# LineMixer_v1_0.net
KiCad netlist of a schematic drawn in EAGLE
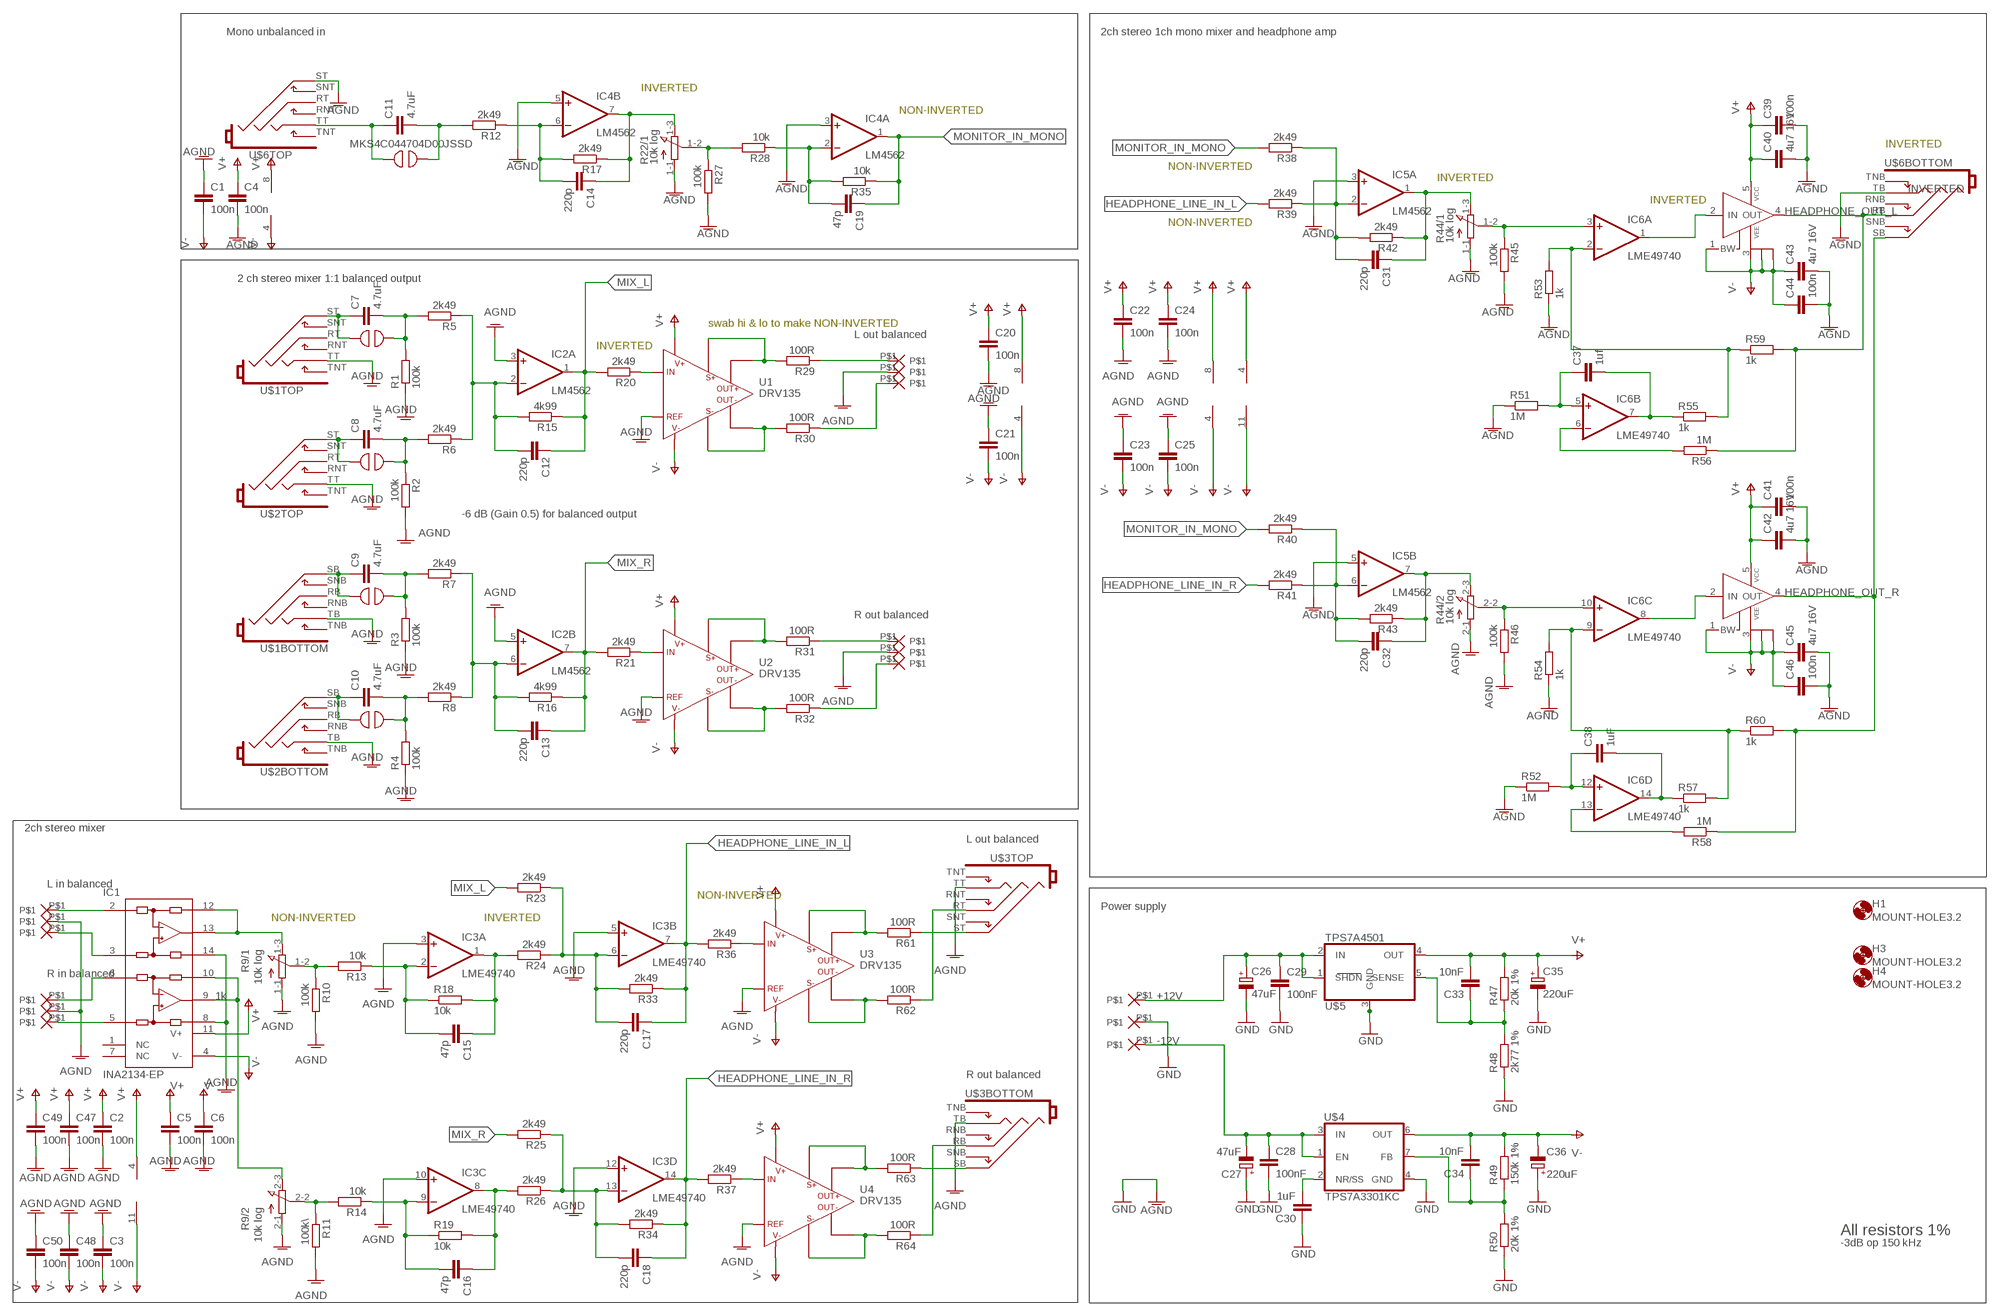
[diagram p0: schematic, sheet 1]

(export (version "E")
  (design (tool "Eeschema 10.0.6"))
  (components
    (comp (ref "C1")
      (value "100n")
      (footprint "eagle-import:C0603")
      (libsource (lib "eagle-import") (part "C-EUC0603"))
    )
    (comp (ref "C2")
      (value "100n")
      (footprint "eagle-import:C0603")
      (libsource (lib "eagle-import") (part "C-EUC0603"))
    )
    (comp (ref "C3")
      (value "100n")
      (footprint "eagle-import:C0603")
      (libsource (lib "eagle-import") (part "C-EUC0603"))
    )
    (comp (ref "C4")
      (value "100n")
      (footprint "eagle-import:C0603")
      (libsource (lib "eagle-import") (part "C-EUC0603"))
    )
    (comp (ref "C5")
      (value "100n")
      (footprint "eagle-import:C0603")
      (libsource (lib "eagle-import") (part "C-EUC0603"))
    )
    (comp (ref "C6")
      (value "100n")
      (footprint "eagle-import:C0603")
      (libsource (lib "eagle-import") (part "C-EUC0603"))
    )
    (comp (ref "C7")
      (value "4.7uF")
      (footprint "eagle-import:C15B7")
      (libsource (lib "eagle-import") (part "C15/7"))
    )
    (comp (ref "C8")
      (value "4.7uF")
      (footprint "eagle-import:C15B7")
      (libsource (lib "eagle-import") (part "C15/7"))
    )
    (comp (ref "C9")
      (value "4.7uF")
      (footprint "eagle-import:C15B7")
      (libsource (lib "eagle-import") (part "C15/7"))
    )
    (comp (ref "C10")
      (value "4.7uF")
      (footprint "eagle-import:C15B7")
      (libsource (lib "eagle-import") (part "C15/7"))
    )
    (comp (ref "C11")
      (value "4.7uF")
      (footprint "eagle-import:C15B7")
      (libsource (lib "eagle-import") (part "C15/7"))
    )
    (comp (ref "C12")
      (value "220p")
      (footprint "eagle-import:C0603K")
      (libsource (lib "eagle-import") (part "C-EUC0603K"))
    )
    (comp (ref "C13")
      (value "220p")
      (footprint "eagle-import:C0603K")
      (libsource (lib "eagle-import") (part "C-EUC0603K"))
    )
    (comp (ref "C14")
      (value "220p")
      (footprint "eagle-import:C0603K")
      (libsource (lib "eagle-import") (part "C-EUC0603K"))
    )
    (comp (ref "C15")
      (value "47p")
      (footprint "eagle-import:C0603K")
      (libsource (lib "eagle-import") (part "C-EUC0603K"))
    )
    (comp (ref "C16")
      (value "47p")
      (footprint "eagle-import:C0603K")
      (libsource (lib "eagle-import") (part "C-EUC0603K"))
    )
    (comp (ref "C17")
      (value "220p")
      (footprint "eagle-import:C0603K")
      (libsource (lib "eagle-import") (part "C-EUC0603K"))
    )
    (comp (ref "C18")
      (value "220p")
      (footprint "eagle-import:C0603K")
      (libsource (lib "eagle-import") (part "C-EUC0603K"))
    )
    (comp (ref "C19")
      (value "47p")
      (footprint "eagle-import:C0603K")
      (libsource (lib "eagle-import") (part "C-EUC0603K"))
    )
    (comp (ref "C20")
      (value "100n")
      (footprint "eagle-import:C0603")
      (libsource (lib "eagle-import") (part "C-EUC0603"))
    )
    (comp (ref "C21")
      (value "100n")
      (footprint "eagle-import:C0603")
      (libsource (lib "eagle-import") (part "C-EUC0603"))
    )
    (comp (ref "C22")
      (value "100n")
      (footprint "eagle-import:C0603")
      (libsource (lib "eagle-import") (part "C-EUC0603"))
    )
    (comp (ref "C23")
      (value "100n")
      (footprint "eagle-import:C0603")
      (libsource (lib "eagle-import") (part "C-EUC0603"))
    )
    (comp (ref "C24")
      (value "100n")
      (footprint "eagle-import:C0603")
      (libsource (lib "eagle-import") (part "C-EUC0603"))
    )
    (comp (ref "C25")
      (value "100n")
      (footprint "eagle-import:C0603")
      (libsource (lib "eagle-import") (part "C-EUC0603"))
    )
    (comp (ref "C26")
      (value "47uF")
      (footprint "eagle-import:D_7343-31R")
      (libsource (lib "eagle-import") (part "CPOL-EUD/7343-31R"))
    )
    (comp (ref "C27")
      (value "47uF")
      (footprint "eagle-import:D_7343-31R")
      (libsource (lib "eagle-import") (part "CPOL-EUD/7343-31R"))
    )
    (comp (ref "C28")
      (value "100nF")
      (footprint "eagle-import:C0603")
      (libsource (lib "eagle-import") (part "C-EUC0603"))
    )
    (comp (ref "C29")
      (value "100nF")
      (footprint "eagle-import:C0603")
      (libsource (lib "eagle-import") (part "C-EUC0603"))
    )
    (comp (ref "C30")
      (value "1uF")
      (footprint "eagle-import:C0603")
      (libsource (lib "eagle-import") (part "C-EUC0603"))
    )
    (comp (ref "C31")
      (value "220p")
      (footprint "eagle-import:C0603K")
      (libsource (lib "eagle-import") (part "C-EUC0603K"))
    )
    (comp (ref "C32")
      (value "220p")
      (footprint "eagle-import:C0603K")
      (libsource (lib "eagle-import") (part "C-EUC0603K"))
    )
    (comp (ref "C33")
      (value "10nF")
      (footprint "eagle-import:C0603")
      (libsource (lib "eagle-import") (part "C-EUC0603"))
    )
    (comp (ref "C34")
      (value "10nF")
      (footprint "eagle-import:C0603")
      (libsource (lib "eagle-import") (part "C-EUC0603"))
    )
    (comp (ref "C35")
      (value "220uF")
      (footprint "eagle-import:D_7343-31R")
      (libsource (lib "eagle-import") (part "CPOL-EUD/7343-31R"))
    )
    (comp (ref "C36")
      (value "220uF")
      (footprint "eagle-import:D_7343-31R")
      (libsource (lib "eagle-import") (part "CPOL-EUD/7343-31R"))
    )
    (comp (ref "C37")
      (value "1uf")
      (footprint "eagle-import:C0603")
      (libsource (lib "eagle-import") (part "C-EUC0603"))
    )
    (comp (ref "C38")
      (value "1uF")
      (footprint "eagle-import:C0603")
      (libsource (lib "eagle-import") (part "C-EUC0603"))
    )
    (comp (ref "C39")
      (value "100n")
      (footprint "eagle-import:C0603")
      (libsource (lib "eagle-import") (part "C-EUC0603"))
    )
    (comp (ref "C40")
      (value "4u7 16V")
      (footprint "eagle-import:C1206")
      (libsource (lib "eagle-import") (part "C-EUC1206"))
    )
    (comp (ref "C41")
      (value "100n")
      (footprint "eagle-import:C0603")
      (libsource (lib "eagle-import") (part "C-EUC0603"))
    )
    (comp (ref "C42")
      (value "4u7 16V")
      (footprint "eagle-import:C1206")
      (libsource (lib "eagle-import") (part "C-EUC1206"))
    )
    (comp (ref "C43")
      (value "4u7 16V")
      (footprint "eagle-import:C1206")
      (libsource (lib "eagle-import") (part "C-EUC1206"))
    )
    (comp (ref "C44")
      (value "100n")
      (footprint "eagle-import:C0603")
      (libsource (lib "eagle-import") (part "C-EUC0603"))
    )
    (comp (ref "C45")
      (value "4u7 16V")
      (footprint "eagle-import:C1206")
      (libsource (lib "eagle-import") (part "C-EUC1206"))
    )
    (comp (ref "C46")
      (value "100n")
      (footprint "eagle-import:C0603")
      (libsource (lib "eagle-import") (part "C-EUC0603"))
    )
    (comp (ref "C47")
      (value "100n")
      (footprint "eagle-import:C0603")
      (libsource (lib "eagle-import") (part "C-EUC0603"))
    )
    (comp (ref "C48")
      (value "100n")
      (footprint "eagle-import:C0603")
      (libsource (lib "eagle-import") (part "C-EUC0603"))
    )
    (comp (ref "C49")
      (value "100n")
      (footprint "eagle-import:C0603")
      (libsource (lib "eagle-import") (part "C-EUC0603"))
    )
    (comp (ref "C50")
      (value "100n")
      (footprint "eagle-import:C0603")
      (libsource (lib "eagle-import") (part "C-EUC0603"))
    )
    (comp (ref "H1")
      (value "MOUNT-HOLE3.2")
      (footprint "eagle-import:3,2")
      (libsource (lib "eagle-import") (part "MOUNT-HOLE3.2"))
    )
    (comp (ref "H3")
      (value "MOUNT-HOLE3.2")
      (footprint "eagle-import:3,2")
      (libsource (lib "eagle-import") (part "MOUNT-HOLE3.2"))
    )
    (comp (ref "H4")
      (value "MOUNT-HOLE3.2")
      (footprint "eagle-import:3,2")
      (libsource (lib "eagle-import") (part "MOUNT-HOLE3.2"))
    )
    (comp (ref "IC1")
      (value "INA2134-EP")
      (footprint "eagle-import:SO14")
      (fields (field (name "MF") "TEXAS INSTRUMENTS") (field (name "MPN") "INA2134UA"))
      (libsource (lib "eagle-import") (part "INA2134U"))
    )
    (comp (ref "IC2")
      (value "LM4562")
      (footprint "eagle-import:SO08")
      (libsource (lib "eagle-import") (part "4558DLM"))
    )
    (comp (ref "IC3")
      (value "LME49740")
      (footprint "eagle-import:SO14")
      (libsource (lib "eagle-import") (part "TL074D"))
    )
    (comp (ref "IC4")
      (value "LM4562")
      (footprint "eagle-import:SO08")
      (libsource (lib "eagle-import") (part "4558DLM"))
    )
    (comp (ref "IC5")
      (value "LM4562")
      (footprint "eagle-import:SO08")
      (libsource (lib "eagle-import") (part "4558DLM"))
    )
    (comp (ref "IC6")
      (value "LME49740")
      (footprint "eagle-import:SO14")
      (libsource (lib "eagle-import") (part "TL074D"))
    )
    (comp (ref "IC7")
      (value "LME49600")
      (footprint "eagle-import:TS5B")
      (libsource (lib "eagle-import") (part "LME49600"))
    )
    (comp (ref "IC8")
      (value "LME49600")
      (footprint "eagle-import:TS5B")
      (libsource (lib "eagle-import") (part "LME49600"))
    )
    (comp (ref "R1")
      (value "100k")
      (footprint "eagle-import:0207_7")
      (libsource (lib "eagle-import") (part "R-EU_0207/7"))
    )
    (comp (ref "R2")
      (value "100k")
      (footprint "eagle-import:0207_7")
      (libsource (lib "eagle-import") (part "R-EU_0207/7"))
    )
    (comp (ref "R3")
      (value "100k")
      (footprint "eagle-import:0207_7")
      (libsource (lib "eagle-import") (part "R-EU_0207/7"))
    )
    (comp (ref "R4")
      (value "100k")
      (footprint "eagle-import:0207_7")
      (libsource (lib "eagle-import") (part "R-EU_0207/7"))
    )
    (comp (ref "R5")
      (value "2k49")
      (footprint "eagle-import:0207_7")
      (libsource (lib "eagle-import") (part "R-EU_0207/7"))
    )
    (comp (ref "R6")
      (value "2k49")
      (footprint "eagle-import:0207_7")
      (libsource (lib "eagle-import") (part "R-EU_0207/7"))
    )
    (comp (ref "R7")
      (value "2k49")
      (footprint "eagle-import:0207_7")
      (libsource (lib "eagle-import") (part "R-EU_0207/7"))
    )
    (comp (ref "R8")
      (value "2k49")
      (footprint "eagle-import:0207_7")
      (libsource (lib "eagle-import") (part "R-EU_0207/7"))
    )
    (comp (ref "R9")
      (value "10k log")
      (footprint "eagle-import:3RP_1610G")
      (libsource (lib "eagle-import") (part "3RP/1610G"))
    )
    (comp (ref "R10")
      (value "100k")
      (footprint "eagle-import:0207_7")
      (libsource (lib "eagle-import") (part "R-EU_0207/7"))
    )
    (comp (ref "R11")
      (value "100k\\")
      (footprint "eagle-import:0207_7")
      (libsource (lib "eagle-import") (part "R-EU_0207/7"))
    )
    (comp (ref "R12")
      (value "2k49")
      (footprint "eagle-import:0207_7")
      (libsource (lib "eagle-import") (part "R-EU_0207/7"))
    )
    (comp (ref "R13")
      (value "10k")
      (footprint "eagle-import:0207_7")
      (libsource (lib "eagle-import") (part "R-EU_0207/7"))
    )
    (comp (ref "R14")
      (value "10k")
      (footprint "eagle-import:0207_7")
      (libsource (lib "eagle-import") (part "R-EU_0207/7"))
    )
    (comp (ref "R15")
      (value "4k99")
      (footprint "eagle-import:0207_7")
      (libsource (lib "eagle-import") (part "R-EU_0207/7"))
    )
    (comp (ref "R16")
      (value "4k99")
      (footprint "eagle-import:0207_7")
      (libsource (lib "eagle-import") (part "R-EU_0207/7"))
    )
    (comp (ref "R17")
      (value "2k49")
      (footprint "eagle-import:0207_7")
      (libsource (lib "eagle-import") (part "R-EU_0207/7"))
    )
    (comp (ref "R18")
      (value "10k")
      (footprint "eagle-import:0207_7")
      (libsource (lib "eagle-import") (part "R-EU_0207/7"))
    )
    (comp (ref "R19")
      (value "10k")
      (footprint "eagle-import:0207_7")
      (libsource (lib "eagle-import") (part "R-EU_0207/7"))
    )
    (comp (ref "R20")
      (value "2k49")
      (footprint "eagle-import:0207_7")
      (libsource (lib "eagle-import") (part "R-EU_0207/7"))
    )
    (comp (ref "R21")
      (value "2k49")
      (footprint "eagle-import:0207_7")
      (libsource (lib "eagle-import") (part "R-EU_0207/7"))
    )
    (comp (ref "R22")
      (value "10k log")
      (footprint "eagle-import:3RP_1610G")
      (libsource (lib "eagle-import") (part "3RP/1610G"))
    )
    (comp (ref "R23")
      (value "2k49")
      (footprint "eagle-import:0207_7")
      (libsource (lib "eagle-import") (part "R-EU_0207/7"))
    )
    (comp (ref "R24")
      (value "2k49")
      (footprint "eagle-import:0207_7")
      (libsource (lib "eagle-import") (part "R-EU_0207/7"))
    )
    (comp (ref "R25")
      (value "2k49")
      (footprint "eagle-import:0207_7")
      (libsource (lib "eagle-import") (part "R-EU_0207/7"))
    )
    (comp (ref "R26")
      (value "2k49")
      (footprint "eagle-import:0207_7")
      (libsource (lib "eagle-import") (part "R-EU_0207/7"))
    )
    (comp (ref "R27")
      (value "100k")
      (footprint "eagle-import:0207_7")
      (libsource (lib "eagle-import") (part "R-EU_0207/7"))
    )
    (comp (ref "R28")
      (value "10k")
      (footprint "eagle-import:0207_7")
      (libsource (lib "eagle-import") (part "R-EU_0207/7"))
    )
    (comp (ref "R29")
      (value "100R")
      (footprint "eagle-import:0207_7")
      (libsource (lib "eagle-import") (part "R-EU_0207/7"))
    )
    (comp (ref "R30")
      (value "100R")
      (footprint "eagle-import:0207_7")
      (libsource (lib "eagle-import") (part "R-EU_0207/7"))
    )
    (comp (ref "R31")
      (value "100R")
      (footprint "eagle-import:0207_7")
      (libsource (lib "eagle-import") (part "R-EU_0207/7"))
    )
    (comp (ref "R32")
      (value "100R")
      (footprint "eagle-import:0207_7")
      (libsource (lib "eagle-import") (part "R-EU_0207/7"))
    )
    (comp (ref "R33")
      (value "2k49")
      (footprint "eagle-import:0207_7")
      (libsource (lib "eagle-import") (part "R-EU_0207/7"))
    )
    (comp (ref "R34")
      (value "2k49")
      (footprint "eagle-import:0207_7")
      (libsource (lib "eagle-import") (part "R-EU_0207/7"))
    )
    (comp (ref "R35")
      (value "10k")
      (footprint "eagle-import:0207_7")
      (libsource (lib "eagle-import") (part "R-EU_0207/7"))
    )
    (comp (ref "R36")
      (value "2k49")
      (footprint "eagle-import:0207_7")
      (libsource (lib "eagle-import") (part "R-EU_0207/7"))
    )
    (comp (ref "R37")
      (value "2k49")
      (footprint "eagle-import:0207_7")
      (libsource (lib "eagle-import") (part "R-EU_0207/7"))
    )
    (comp (ref "R38")
      (value "2k49")
      (footprint "eagle-import:0207_7")
      (libsource (lib "eagle-import") (part "R-EU_0207/7"))
    )
    (comp (ref "R39")
      (value "2k49")
      (footprint "eagle-import:0207_7")
      (libsource (lib "eagle-import") (part "R-EU_0207/7"))
    )
    (comp (ref "R40")
      (value "2k49")
      (footprint "eagle-import:0207_7")
      (libsource (lib "eagle-import") (part "R-EU_0207/7"))
    )
    (comp (ref "R41")
      (value "2k49")
      (footprint "eagle-import:0207_7")
      (libsource (lib "eagle-import") (part "R-EU_0207/7"))
    )
    (comp (ref "R42")
      (value "2k49")
      (footprint "eagle-import:0207_7")
      (libsource (lib "eagle-import") (part "R-EU_0207/7"))
    )
    (comp (ref "R43")
      (value "2k49")
      (footprint "eagle-import:0207_7")
      (libsource (lib "eagle-import") (part "R-EU_0207/7"))
    )
    (comp (ref "R44")
      (value "10k log")
      (footprint "eagle-import:3RP_1610G")
      (libsource (lib "eagle-import") (part "3RP/1610G"))
    )
    (comp (ref "R45")
      (value "100k")
      (footprint "eagle-import:0207_7")
      (libsource (lib "eagle-import") (part "R-EU_0207/7"))
    )
    (comp (ref "R46")
      (value "100k")
      (footprint "eagle-import:0207_7")
      (libsource (lib "eagle-import") (part "R-EU_0207/7"))
    )
    (comp (ref "R47")
      (value "20k 1%")
      (footprint "eagle-import:R0603")
      (libsource (lib "eagle-import") (part "R-EU_R0603"))
    )
    (comp (ref "R48")
      (value "2k77 1%")
      (footprint "eagle-import:R0603")
      (libsource (lib "eagle-import") (part "R-EU_R0603"))
    )
    (comp (ref "R49")
      (value "150k 1%")
      (footprint "eagle-import:R0603")
      (libsource (lib "eagle-import") (part "R-EU_R0603"))
    )
    (comp (ref "R50")
      (value "20k 1%")
      (footprint "eagle-import:R0603")
      (libsource (lib "eagle-import") (part "R-EU_R0603"))
    )
    (comp (ref "R51")
      (value "1M")
      (footprint "eagle-import:0207_7")
      (libsource (lib "eagle-import") (part "R-EU_0207/7"))
    )
    (comp (ref "R52")
      (value "1M")
      (footprint "eagle-import:0207_7")
      (libsource (lib "eagle-import") (part "R-EU_0207/7"))
    )
    (comp (ref "R53")
      (value "1k")
      (footprint "eagle-import:0207_7")
      (libsource (lib "eagle-import") (part "R-EU_0207/7"))
    )
    (comp (ref "R54")
      (value "1k")
      (footprint "eagle-import:0207_7")
      (libsource (lib "eagle-import") (part "R-EU_0207/7"))
    )
    (comp (ref "R55")
      (value "1k")
      (footprint "eagle-import:0207_7")
      (libsource (lib "eagle-import") (part "R-EU_0207/7"))
    )
    (comp (ref "R56")
      (value "1M")
      (footprint "eagle-import:0207_7")
      (libsource (lib "eagle-import") (part "R-EU_0207/7"))
    )
    (comp (ref "R57")
      (value "1k")
      (footprint "eagle-import:0207_7")
      (libsource (lib "eagle-import") (part "R-EU_0207/7"))
    )
    (comp (ref "R58")
      (value "1M")
      (footprint "eagle-import:0207_7")
      (libsource (lib "eagle-import") (part "R-EU_0207/7"))
    )
    (comp (ref "R59")
      (value "1k")
      (footprint "eagle-import:0207_7")
      (libsource (lib "eagle-import") (part "R-EU_0207/7"))
    )
    (comp (ref "R60")
      (value "1k")
      (footprint "eagle-import:0207_7")
      (libsource (lib "eagle-import") (part "R-EU_0207/7"))
    )
    (comp (ref "R61")
      (value "100R")
      (footprint "eagle-import:0207_7")
      (libsource (lib "eagle-import") (part "R-EU_0207/7"))
    )
    (comp (ref "R62")
      (value "100R")
      (footprint "eagle-import:0207_7")
      (libsource (lib "eagle-import") (part "R-EU_0207/7"))
    )
    (comp (ref "R63")
      (value "100R")
      (footprint "eagle-import:0207_7")
      (libsource (lib "eagle-import") (part "R-EU_0207/7"))
    )
    (comp (ref "R64")
      (value "100R")
      (footprint "eagle-import:0207_7")
      (libsource (lib "eagle-import") (part "R-EU_0207/7"))
    )
    (comp (ref "S1")
      (value "SOLDERLINK")
      (footprint "eagle-import:SOLDERLINK")
      (libsource (lib "eagle-import") (part "SOLDERLINK"))
    )
    (comp (ref "S2")
      (value "SOLDERLINK")
      (footprint "eagle-import:SOLDERLINK")
      (libsource (lib "eagle-import") (part "SOLDERLINK"))
    )
    (comp (ref "S3")
      (value "SOLDERLINK")
      (footprint "eagle-import:SOLDERLINK")
      (libsource (lib "eagle-import") (part "SOLDERLINK"))
    )
    (comp (ref "S4")
      (value "SOLDERLINK")
      (footprint "eagle-import:SOLDERLINK")
      (libsource (lib "eagle-import") (part "SOLDERLINK"))
    )
    (comp (ref "S5")
      (value "SOLDERLINK")
      (footprint "eagle-import:SOLDERLINK")
      (libsource (lib "eagle-import") (part "SOLDERLINK"))
    )
    (comp (ref "U$1")
      (value "NSJ12HF-1")
      (footprint "eagle-import:NSJ12HF-1")
      (libsource (lib "eagle-import") (part "NSJ12HF-1"))
    )
    (comp (ref "U$2")
      (value "NSJ12HF-1")
      (footprint "eagle-import:NSJ12HF-1")
      (libsource (lib "eagle-import") (part "NSJ12HF-1"))
    )
    (comp (ref "U$3")
      (value "NSJ12HF-1")
      (footprint "eagle-import:NSJ12HF-1")
      (libsource (lib "eagle-import") (part "NSJ12HF-1"))
    )
    (comp (ref "U$4")
      (value "TPS7A3301KC")
      (footprint "eagle-import:TO220-7")
      (libsource (lib "eagle-import") (part "TPS7A3301KC"))
    )
    (comp (ref "U$5")
      (value "TPS7A4501")
      (footprint "eagle-import:SOT223-5")
      (libsource (lib "eagle-import") (part "TPS7A4501"))
    )
    (comp (ref "U$6")
      (value "NSJ12HF-1")
      (footprint "eagle-import:NSJ12HF-1")
      (libsource (lib "eagle-import") (part "NSJ12HF-1"))
    )
    (comp (ref "U$7")
      (value "PAD1.5MM")
      (footprint "eagle-import:PAD_1.5MM")
      (libsource (lib "eagle-import") (part "PAD1.5MM"))
    )
    (comp (ref "U$8")
      (value "PAD1.5MM")
      (footprint "eagle-import:PAD_1.5MM")
      (libsource (lib "eagle-import") (part "PAD1.5MM"))
    )
    (comp (ref "U$10")
      (value "PAD1.5MM")
      (footprint "eagle-import:PAD_1.5MM")
      (libsource (lib "eagle-import") (part "PAD1.5MM"))
    )
    (comp (ref "U$11")
      (value "PAD1.5MM")
      (footprint "eagle-import:PAD_1.5MM")
      (libsource (lib "eagle-import") (part "PAD1.5MM"))
    )
    (comp (ref "U$12")
      (value "PAD1.5MM")
      (footprint "eagle-import:PAD_1.5MM")
      (libsource (lib "eagle-import") (part "PAD1.5MM"))
    )
    (comp (ref "U$13")
      (value "PAD1.5MM")
      (footprint "eagle-import:PAD_1.5MM")
      (libsource (lib "eagle-import") (part "PAD1.5MM"))
    )
    (comp (ref "U$14")
      (value "PAD1.5MM")
      (footprint "eagle-import:PAD_1.5MM")
      (libsource (lib "eagle-import") (part "PAD1.5MM"))
    )
    (comp (ref "U$15")
      (value "PAD1.5MM")
      (footprint "eagle-import:PAD_1.5MM")
      (libsource (lib "eagle-import") (part "PAD1.5MM"))
    )
    (comp (ref "U$16")
      (value "PAD1.5MM")
      (footprint "eagle-import:PAD_1.5MM")
      (libsource (lib "eagle-import") (part "PAD1.5MM"))
    )
    (comp (ref "U$17")
      (value "PAD1.5MM")
      (footprint "eagle-import:PAD_1.5MM")
      (libsource (lib "eagle-import") (part "PAD1.5MM"))
    )
    (comp (ref "U$18")
      (value "PAD1.5MM")
      (footprint "eagle-import:PAD_1.5MM")
      (libsource (lib "eagle-import") (part "PAD1.5MM"))
    )
    (comp (ref "U$19")
      (value "PAD1.5MM")
      (footprint "eagle-import:PAD_1.5MM")
      (libsource (lib "eagle-import") (part "PAD1.5MM"))
    )
    (comp (ref "U$20")
      (value "PAD1.5MM")
      (footprint "eagle-import:PAD_1.5MM")
      (libsource (lib "eagle-import") (part "PAD1.5MM"))
    )
    (comp (ref "U$21")
      (value "PAD1.5MM")
      (footprint "eagle-import:PAD_1.5MM")
      (libsource (lib "eagle-import") (part "PAD1.5MM"))
    )
    (comp (ref "U$22")
      (value "PAD1.5MM")
      (footprint "eagle-import:PAD_1.5MM")
      (libsource (lib "eagle-import") (part "PAD1.5MM"))
    )
    (comp (ref "U1")
      (value "DRV135")
      (footprint "eagle-import:SO-8")
      (libsource (lib "eagle-import") (part "DRV134SO-8"))
    )
    (comp (ref "U2")
      (value "DRV135")
      (footprint "eagle-import:SO-8")
      (libsource (lib "eagle-import") (part "DRV134SO-8"))
    )
    (comp (ref "U3")
      (value "DRV135")
      (footprint "eagle-import:SO-8")
      (libsource (lib "eagle-import") (part "DRV134SO-8"))
    )
    (comp (ref "U4")
      (value "DRV135")
      (footprint "eagle-import:SO-8")
      (libsource (lib "eagle-import") (part "DRV134SO-8"))
    )
  )
  (nets
    (net (code "1") (name "/+12V") (class "Default")
      (node (ref "C26") (pin "+") (pinfunction "+_+") (pintype "passive"))
      (node (ref "C29") (pin "1") (pinfunction "1_1") (pintype "passive"))
      (node (ref "U$20") (pin "P$1") (pinfunction "P$1_P$1") (pintype "bidirectional"))
      (node (ref "U$5") (pin "1") (pinfunction "SHDN_1") (pintype "input"))
      (node (ref "U$5") (pin "2") (pinfunction "IN_2") (pintype "power_in"))
    )
    (net (code "2") (name "/-12V") (class "Default")
      (node (ref "C27") (pin "-") (pinfunction "-_-") (pintype "passive"))
      (node (ref "C28") (pin "1") (pinfunction "1_1") (pintype "passive"))
      (node (ref "U$22") (pin "P$1") (pinfunction "P$1_P$1") (pintype "bidirectional"))
      (node (ref "U$4") (pin "1") (pinfunction "EN_1") (pintype "bidirectional"))
      (node (ref "U$4") (pin "3") (pinfunction "IN_3") (pintype "bidirectional"))
    )
    (net (code "3") (name "/HEADPHONE_OUT_L") (class "Default")
      (node (ref "IC7") (pin "4") (pinfunction "OUT_4") (pintype "output"))
      (node (ref "R56") (pin "1") (pinfunction "1_1") (pintype "passive"))
      (node (ref "R59") (pin "2") (pinfunction "2_2") (pintype "passive"))
      (node (ref "U$6") (pin "RB") (pinfunction "R_RB") (pintype "bidirectional"))
    )
    (net (code "4") (name "/HEADPHONE_OUT_R") (class "Default")
      (node (ref "IC8") (pin "4") (pinfunction "OUT_4") (pintype "output"))
      (node (ref "R58") (pin "1") (pinfunction "1_1") (pintype "passive"))
      (node (ref "R60") (pin "2") (pinfunction "2_2") (pintype "passive"))
      (node (ref "U$6") (pin "SB") (pinfunction "S_SB") (pintype "bidirectional"))
    )
    (net (code "5") (name "AGND") (class "Default")
      (node (ref "C1") (pin "1") (pinfunction "1_1") (pintype "passive"))
      (node (ref "C2") (pin "2") (pinfunction "2_2") (pintype "passive"))
      (node (ref "C20") (pin "2") (pinfunction "2_2") (pintype "passive"))
      (node (ref "C21") (pin "1") (pinfunction "1_1") (pintype "passive"))
      (node (ref "C22") (pin "2") (pinfunction "2_2") (pintype "passive"))
      (node (ref "C23") (pin "1") (pinfunction "1_1") (pintype "passive"))
      (node (ref "C24") (pin "2") (pinfunction "2_2") (pintype "passive"))
      (node (ref "C25") (pin "1") (pinfunction "1_1") (pintype "passive"))
      (node (ref "C26") (pin "-") (pinfunction "-_-") (pintype "passive"))
      (node (ref "C27") (pin "+") (pinfunction "+_+") (pintype "passive"))
      (node (ref "C28") (pin "2") (pinfunction "2_2") (pintype "passive"))
      (node (ref "C29") (pin "2") (pinfunction "2_2") (pintype "passive"))
      (node (ref "C3") (pin "1") (pinfunction "1_1") (pintype "passive"))
      (node (ref "C30") (pin "1") (pinfunction "1_1") (pintype "passive"))
      (node (ref "C35") (pin "-") (pinfunction "-_-") (pintype "passive"))
      (node (ref "C36") (pin "+") (pinfunction "+_+") (pintype "passive"))
      (node (ref "C39") (pin "2") (pinfunction "2_2") (pintype "passive"))
      (node (ref "C4") (pin "2") (pinfunction "2_2") (pintype "passive"))
      (node (ref "C40") (pin "2") (pinfunction "2_2") (pintype "passive"))
      (node (ref "C41") (pin "2") (pinfunction "2_2") (pintype "passive"))
      (node (ref "C42") (pin "2") (pinfunction "2_2") (pintype "passive"))
      (node (ref "C43") (pin "2") (pinfunction "2_2") (pintype "passive"))
      (node (ref "C44") (pin "2") (pinfunction "2_2") (pintype "passive"))
      (node (ref "C45") (pin "2") (pinfunction "2_2") (pintype "passive"))
      (node (ref "C46") (pin "2") (pinfunction "2_2") (pintype "passive"))
      (node (ref "C47") (pin "2") (pinfunction "2_2") (pintype "passive"))
      (node (ref "C48") (pin "1") (pinfunction "1_1") (pintype "passive"))
      (node (ref "C49") (pin "2") (pinfunction "2_2") (pintype "passive"))
      (node (ref "C5") (pin "2") (pinfunction "2_2") (pintype "passive"))
      (node (ref "C50") (pin "1") (pinfunction "1_1") (pintype "passive"))
      (node (ref "C6") (pin "2") (pinfunction "2_2") (pintype "passive"))
      (node (ref "IC1") (pin "14") (pinfunction "REFA_14") (pintype "passive"))
      (node (ref "IC1") (pin "8") (pinfunction "REFB_8") (pintype "passive"))
      (node (ref "IC2") (pin "3") (pinfunction "+IN_3") (pintype "input"))
      (node (ref "IC2") (pin "5") (pinfunction "+IN_5") (pintype "input"))
      (node (ref "IC3") (pin "10") (pinfunction "+IN_10") (pintype "input"))
      (node (ref "IC3") (pin "12") (pinfunction "+IN_12") (pintype "input"))
      (node (ref "IC3") (pin "3") (pinfunction "+IN_3") (pintype "input"))
      (node (ref "IC3") (pin "5") (pinfunction "+IN_5") (pintype "input"))
      (node (ref "IC4") (pin "3") (pinfunction "+IN_3") (pintype "input"))
      (node (ref "IC4") (pin "5") (pinfunction "+IN_5") (pintype "input"))
      (node (ref "IC5") (pin "3") (pinfunction "+IN_3") (pintype "input"))
      (node (ref "IC5") (pin "5") (pinfunction "+IN_5") (pintype "input"))
      (node (ref "R1") (pin "1") (pinfunction "1_1") (pintype "passive"))
      (node (ref "R10") (pin "2") (pinfunction "2_2") (pintype "passive"))
      (node (ref "R11") (pin "2") (pinfunction "2_2") (pintype "passive"))
      (node (ref "R2") (pin "2") (pinfunction "2_2") (pintype "passive"))
      (node (ref "R22") (pin "1-1") (pinfunction "A_1-1") (pintype "passive"))
      (node (ref "R27") (pin "2") (pinfunction "2_2") (pintype "passive"))
      (node (ref "R3") (pin "1") (pinfunction "1_1") (pintype "passive"))
      (node (ref "R4") (pin "1") (pinfunction "1_1") (pintype "passive"))
      (node (ref "R44") (pin "1-1") (pinfunction "A_1-1") (pintype "passive"))
      (node (ref "R44") (pin "2-1") (pinfunction "A_2-1") (pintype "passive"))
      (node (ref "R45") (pin "2") (pinfunction "2_2") (pintype "passive"))
      (node (ref "R46") (pin "2") (pinfunction "2_2") (pintype "passive"))
      (node (ref "R48") (pin "1") (pinfunction "1_1") (pintype "passive"))
      (node (ref "R50") (pin "1") (pinfunction "1_1") (pintype "passive"))
      (node (ref "R51") (pin "1") (pinfunction "1_1") (pintype "passive"))
      (node (ref "R52") (pin "1") (pinfunction "1_1") (pintype "passive"))
      (node (ref "R53") (pin "1") (pinfunction "1_1") (pintype "passive"))
      (node (ref "R54") (pin "1") (pinfunction "1_1") (pintype "passive"))
      (node (ref "R9") (pin "1-1") (pinfunction "A_1-1") (pintype "passive"))
      (node (ref "R9") (pin "2-1") (pinfunction "A_2-1") (pintype "passive"))
      (node (ref "U$1") (pin "TB") (pinfunction "T_TB") (pintype "bidirectional"))
      (node (ref "U$1") (pin "TT") (pinfunction "T_TT") (pintype "bidirectional"))
      (node (ref "U$12") (pin "P$1") (pinfunction "P$1_P$1") (pintype "bidirectional"))
      (node (ref "U$15") (pin "P$1") (pinfunction "P$1_P$1") (pintype "bidirectional"))
      (node (ref "U$18") (pin "P$1") (pinfunction "P$1_P$1") (pintype "bidirectional"))
      (node (ref "U$2") (pin "TB") (pinfunction "T_TB") (pintype "bidirectional"))
      (node (ref "U$2") (pin "TT") (pinfunction "T_TT") (pintype "bidirectional"))
      (node (ref "U$21") (pin "P$1") (pinfunction "P$1_P$1") (pintype "bidirectional"))
      (node (ref "U$3") (pin "TB") (pinfunction "T_TB") (pintype "bidirectional"))
      (node (ref "U$3") (pin "TT") (pinfunction "T_TT") (pintype "bidirectional"))
      (node (ref "U$4") (pin "4") (pinfunction "GND_4") (pintype "bidirectional"))
      (node (ref "U$5") (pin "3") (pinfunction "GND_3") (pintype "power_in"))
      (node (ref "U$5") (pin "TAB") (pinfunction "GND_TAB") (pintype "power_in"))
      (node (ref "U$6") (pin "ST") (pinfunction "S_ST") (pintype "bidirectional"))
      (node (ref "U$6") (pin "TB") (pinfunction "T_TB") (pintype "bidirectional"))
      (node (ref "U$8") (pin "P$1") (pinfunction "P$1_P$1") (pintype "bidirectional"))
      (node (ref "U1") (pin "P3") (pinfunction "REF_P3") (pintype "input"))
      (node (ref "U2") (pin "P3") (pinfunction "REF_P3") (pintype "input"))
      (node (ref "U3") (pin "P3") (pinfunction "REF_P3") (pintype "input"))
      (node (ref "U4") (pin "P3") (pinfunction "REF_P3") (pintype "input"))
    )
    (net (code "6") (name "HEADPHONE_LINE_IN_L") (class "Default")
      (node (ref "C17") (pin "1") (pinfunction "1_1") (pintype "passive"))
      (node (ref "IC3") (pin "7") (pinfunction "OUT_7") (pintype "output"))
      (node (ref "R33") (pin "1") (pinfunction "1_1") (pintype "passive"))
      (node (ref "R36") (pin "2") (pinfunction "2_2") (pintype "passive"))
      (node (ref "R39") (pin "2") (pinfunction "2_2") (pintype "passive"))
    )
    (net (code "7") (name "HEADPHONE_LINE_IN_R") (class "Default")
      (node (ref "C18") (pin "1") (pinfunction "1_1") (pintype "passive"))
      (node (ref "IC3") (pin "14") (pinfunction "OUT_14") (pintype "output"))
      (node (ref "R34") (pin "1") (pinfunction "1_1") (pintype "passive"))
      (node (ref "R37") (pin "2") (pinfunction "2_2") (pintype "passive"))
      (node (ref "R41") (pin "2") (pinfunction "2_2") (pintype "passive"))
    )
    (net (code "8") (name "MIX_L") (class "Default")
      (node (ref "C12") (pin "1") (pinfunction "1_1") (pintype "passive"))
      (node (ref "IC2") (pin "1") (pinfunction "OUT_1") (pintype "output"))
      (node (ref "R15") (pin "1") (pinfunction "1_1") (pintype "passive"))
      (node (ref "R20") (pin "2") (pinfunction "2_2") (pintype "passive"))
      (node (ref "R23") (pin "2") (pinfunction "2_2") (pintype "passive"))
    )
    (net (code "9") (name "MIX_R") (class "Default")
      (node (ref "C13") (pin "1") (pinfunction "1_1") (pintype "passive"))
      (node (ref "IC2") (pin "7") (pinfunction "OUT_7") (pintype "output"))
      (node (ref "R16") (pin "1") (pinfunction "1_1") (pintype "passive"))
      (node (ref "R21") (pin "2") (pinfunction "2_2") (pintype "passive"))
      (node (ref "R25") (pin "2") (pinfunction "2_2") (pintype "passive"))
    )
    (net (code "10") (name "MONITOR_IN_MONO") (class "Default")
      (node (ref "C19") (pin "1") (pinfunction "1_1") (pintype "passive"))
      (node (ref "IC4") (pin "1") (pinfunction "OUT_1") (pintype "output"))
      (node (ref "R35") (pin "1") (pinfunction "1_1") (pintype "passive"))
      (node (ref "R38") (pin "2") (pinfunction "2_2") (pintype "passive"))
      (node (ref "R40") (pin "2") (pinfunction "2_2") (pintype "passive"))
    )
    (net (code "11") (name "Net-(C7-Pad2)") (class "Default")
      (node (ref "C7") (pin "2") (pinfunction "2_2") (pintype "passive"))
      (node (ref "R1") (pin "2") (pinfunction "2_2") (pintype "passive"))
      (node (ref "R5") (pin "2") (pinfunction "2_2") (pintype "passive"))
      (node (ref "S1") (pin "P$1") (pinfunction "P$1_P$1") (pintype "passive"))
    )
    (net (code "12") (name "Net-(C8-Pad2)") (class "Default")
      (node (ref "C8") (pin "2") (pinfunction "2_2") (pintype "passive"))
      (node (ref "R2") (pin "1") (pinfunction "1_1") (pintype "passive"))
      (node (ref "R6") (pin "2") (pinfunction "2_2") (pintype "passive"))
      (node (ref "S2") (pin "P$1") (pinfunction "P$1_P$1") (pintype "passive"))
    )
    (net (code "13") (name "Net-(C9-Pad2)") (class "Default")
      (node (ref "C9") (pin "2") (pinfunction "2_2") (pintype "passive"))
      (node (ref "R3") (pin "2") (pinfunction "2_2") (pintype "passive"))
      (node (ref "R7") (pin "2") (pinfunction "2_2") (pintype "passive"))
      (node (ref "S3") (pin "P$1") (pinfunction "P$1_P$1") (pintype "passive"))
    )
    (net (code "14") (name "Net-(C10-Pad2)") (class "Default")
      (node (ref "C10") (pin "2") (pinfunction "2_2") (pintype "passive"))
      (node (ref "R4") (pin "2") (pinfunction "2_2") (pintype "passive"))
      (node (ref "R8") (pin "2") (pinfunction "2_2") (pintype "passive"))
      (node (ref "S4") (pin "P$1") (pinfunction "P$1_P$1") (pintype "passive"))
    )
    (net (code "15") (name "Net-(C11-Pad2)") (class "Default")
      (node (ref "C11") (pin "2") (pinfunction "2_2") (pintype "passive"))
      (node (ref "R12") (pin "2") (pinfunction "2_2") (pintype "passive"))
      (node (ref "S5") (pin "P$1") (pinfunction "P$1_P$1") (pintype "passive"))
    )
    (net (code "16") (name "Net-(IC1-+INA)") (class "Default")
      (node (ref "IC1") (pin "3") (pinfunction "+INA_3") (pintype "input"))
      (node (ref "U$10") (pin "P$1") (pinfunction "P$1_P$1") (pintype "bidirectional"))
    )
    (net (code "17") (name "Net-(IC1-+INB)") (class "Default")
      (node (ref "IC1") (pin "5") (pinfunction "+INB_5") (pintype "input"))
      (node (ref "U$13") (pin "P$1") (pinfunction "P$1_P$1") (pintype "bidirectional"))
    )
    (net (code "18") (name "Net-(IC1--INA)") (class "Default")
      (node (ref "IC1") (pin "2") (pinfunction "-INA_2") (pintype "input"))
      (node (ref "U$7") (pin "P$1") (pinfunction "P$1_P$1") (pintype "bidirectional"))
    )
    (net (code "19") (name "Net-(IC1--INB)") (class "Default")
      (node (ref "IC1") (pin "6") (pinfunction "-INB_6") (pintype "input"))
      (node (ref "U$11") (pin "P$1") (pinfunction "P$1_P$1") (pintype "bidirectional"))
    )
    (net (code "20") (name "Net-(IC1-OUTA)") (class "Default")
      (node (ref "IC1") (pin "12") (pinfunction "SENSEA_12") (pintype "passive"))
      (node (ref "IC1") (pin "13") (pinfunction "OUTA_13") (pintype "output"))
      (node (ref "R9") (pin "1-3") (pinfunction "E_1-3") (pintype "passive"))
    )
    (net (code "21") (name "Net-(IC1-OUTB)") (class "Default")
      (node (ref "IC1") (pin "10") (pinfunction "SENSEB_10") (pintype "passive"))
      (node (ref "IC1") (pin "9") (pinfunction "OUTB_9") (pintype "output"))
      (node (ref "R9") (pin "2-3") (pinfunction "E_2-3") (pintype "passive"))
    )
    (net (code "22") (name "Net-(IC2A--IN)") (class "Default")
      (node (ref "C12") (pin "2") (pinfunction "2_2") (pintype "passive"))
      (node (ref "IC2") (pin "2") (pinfunction "-IN_2") (pintype "input"))
      (node (ref "R15") (pin "2") (pinfunction "2_2") (pintype "passive"))
      (node (ref "R5") (pin "1") (pinfunction "1_1") (pintype "passive"))
      (node (ref "R6") (pin "1") (pinfunction "1_1") (pintype "passive"))
    )
    (net (code "23") (name "Net-(IC2B--IN)") (class "Default")
      (node (ref "C13") (pin "2") (pinfunction "2_2") (pintype "passive"))
      (node (ref "IC2") (pin "6") (pinfunction "-IN_6") (pintype "input"))
      (node (ref "R16") (pin "2") (pinfunction "2_2") (pintype "passive"))
      (node (ref "R7") (pin "1") (pinfunction "1_1") (pintype "passive"))
      (node (ref "R8") (pin "1") (pinfunction "1_1") (pintype "passive"))
    )
    (net (code "24") (name "Net-(IC3A--IN)") (class "Default")
      (node (ref "C15") (pin "2") (pinfunction "2_2") (pintype "passive"))
      (node (ref "IC3") (pin "2") (pinfunction "-IN_2") (pintype "input"))
      (node (ref "R13") (pin "1") (pinfunction "1_1") (pintype "passive"))
      (node (ref "R18") (pin "1") (pinfunction "1_1") (pintype "passive"))
    )
    (net (code "25") (name "Net-(IC3A-OUT)") (class "Default")
      (node (ref "C15") (pin "1") (pinfunction "1_1") (pintype "passive"))
      (node (ref "IC3") (pin "1") (pinfunction "OUT_1") (pintype "output"))
      (node (ref "R18") (pin "2") (pinfunction "2_2") (pintype "passive"))
      (node (ref "R24") (pin "2") (pinfunction "2_2") (pintype "passive"))
    )
    (net (code "26") (name "Net-(IC3B--IN)") (class "Default")
      (node (ref "C17") (pin "2") (pinfunction "2_2") (pintype "passive"))
      (node (ref "IC3") (pin "6") (pinfunction "-IN_6") (pintype "input"))
      (node (ref "R23") (pin "1") (pinfunction "1_1") (pintype "passive"))
      (node (ref "R24") (pin "1") (pinfunction "1_1") (pintype "passive"))
      (node (ref "R33") (pin "2") (pinfunction "2_2") (pintype "passive"))
    )
    (net (code "27") (name "Net-(IC3C--IN)") (class "Default")
      (node (ref "C16") (pin "2") (pinfunction "2_2") (pintype "passive"))
      (node (ref "IC3") (pin "9") (pinfunction "-IN_9") (pintype "input"))
      (node (ref "R14") (pin "1") (pinfunction "1_1") (pintype "passive"))
      (node (ref "R19") (pin "1") (pinfunction "1_1") (pintype "passive"))
    )
    (net (code "28") (name "Net-(IC3C-OUT)") (class "Default")
      (node (ref "C16") (pin "1") (pinfunction "1_1") (pintype "passive"))
      (node (ref "IC3") (pin "8") (pinfunction "OUT_8") (pintype "output"))
      (node (ref "R19") (pin "2") (pinfunction "2_2") (pintype "passive"))
      (node (ref "R26") (pin "2") (pinfunction "2_2") (pintype "passive"))
    )
    (net (code "29") (name "Net-(IC3D--IN)") (class "Default")
      (node (ref "C18") (pin "2") (pinfunction "2_2") (pintype "passive"))
      (node (ref "IC3") (pin "13") (pinfunction "-IN_13") (pintype "input"))
      (node (ref "R25") (pin "1") (pinfunction "1_1") (pintype "passive"))
      (node (ref "R26") (pin "1") (pinfunction "1_1") (pintype "passive"))
      (node (ref "R34") (pin "2") (pinfunction "2_2") (pintype "passive"))
    )
    (net (code "30") (name "Net-(IC4A--IN)") (class "Default")
      (node (ref "C19") (pin "2") (pinfunction "2_2") (pintype "passive"))
      (node (ref "IC4") (pin "2") (pinfunction "-IN_2") (pintype "input"))
      (node (ref "R28") (pin "1") (pinfunction "1_1") (pintype "passive"))
      (node (ref "R35") (pin "2") (pinfunction "2_2") (pintype "passive"))
    )
    (net (code "31") (name "Net-(IC4B--IN)") (class "Default")
      (node (ref "C14") (pin "2") (pinfunction "2_2") (pintype "passive"))
      (node (ref "IC4") (pin "6") (pinfunction "-IN_6") (pintype "input"))
      (node (ref "R12") (pin "1") (pinfunction "1_1") (pintype "passive"))
      (node (ref "R17") (pin "2") (pinfunction "2_2") (pintype "passive"))
    )
    (net (code "32") (name "Net-(IC4B-OUT)") (class "Default")
      (node (ref "C14") (pin "1") (pinfunction "1_1") (pintype "passive"))
      (node (ref "IC4") (pin "7") (pinfunction "OUT_7") (pintype "output"))
      (node (ref "R17") (pin "1") (pinfunction "1_1") (pintype "passive"))
      (node (ref "R22") (pin "1-3") (pinfunction "E_1-3") (pintype "passive"))
    )
    (net (code "33") (name "Net-(IC5A--IN)") (class "Default")
      (node (ref "C31") (pin "2") (pinfunction "2_2") (pintype "passive"))
      (node (ref "IC5") (pin "2") (pinfunction "-IN_2") (pintype "input"))
      (node (ref "R38") (pin "1") (pinfunction "1_1") (pintype "passive"))
      (node (ref "R39") (pin "1") (pinfunction "1_1") (pintype "passive"))
      (node (ref "R42") (pin "2") (pinfunction "2_2") (pintype "passive"))
    )
    (net (code "34") (name "Net-(IC5A-OUT)") (class "Default")
      (node (ref "C31") (pin "1") (pinfunction "1_1") (pintype "passive"))
      (node (ref "IC5") (pin "1") (pinfunction "OUT_1") (pintype "output"))
      (node (ref "R42") (pin "1") (pinfunction "1_1") (pintype "passive"))
      (node (ref "R44") (pin "1-3") (pinfunction "E_1-3") (pintype "passive"))
    )
    (net (code "35") (name "Net-(IC5B--IN)") (class "Default")
      (node (ref "C32") (pin "2") (pinfunction "2_2") (pintype "passive"))
      (node (ref "IC5") (pin "6") (pinfunction "-IN_6") (pintype "input"))
      (node (ref "R40") (pin "1") (pinfunction "1_1") (pintype "passive"))
      (node (ref "R41") (pin "1") (pinfunction "1_1") (pintype "passive"))
      (node (ref "R43") (pin "2") (pinfunction "2_2") (pintype "passive"))
    )
    (net (code "36") (name "Net-(IC5B-OUT)") (class "Default")
      (node (ref "C32") (pin "1") (pinfunction "1_1") (pintype "passive"))
      (node (ref "IC5") (pin "7") (pinfunction "OUT_7") (pintype "output"))
      (node (ref "R43") (pin "1") (pinfunction "1_1") (pintype "passive"))
      (node (ref "R44") (pin "2-3") (pinfunction "E_2-3") (pintype "passive"))
    )
    (net (code "37") (name "Net-(IC6A-+IN)") (class "Default")
      (node (ref "IC6") (pin "3") (pinfunction "+IN_3") (pintype "input"))
      (node (ref "R44") (pin "1-2") (pinfunction "S_1-2") (pintype "passive"))
      (node (ref "R45") (pin "1") (pinfunction "1_1") (pintype "passive"))
    )
    (net (code "38") (name "Net-(IC6A--IN)") (class "Default")
      (node (ref "IC6") (pin "2") (pinfunction "-IN_2") (pintype "input"))
      (node (ref "R53") (pin "2") (pinfunction "2_2") (pintype "passive"))
      (node (ref "R55") (pin "2") (pinfunction "2_2") (pintype "passive"))
      (node (ref "R59") (pin "1") (pinfunction "1_1") (pintype "passive"))
    )
    (net (code "39") (name "Net-(IC6A-OUT)") (class "Default")
      (node (ref "IC6") (pin "1") (pinfunction "OUT_1") (pintype "output"))
      (node (ref "IC7") (pin "2") (pinfunction "IN_2") (pintype "input"))
    )
    (net (code "40") (name "Net-(IC6B-+IN)") (class "Default")
      (node (ref "C37") (pin "1") (pinfunction "1_1") (pintype "passive"))
      (node (ref "IC6") (pin "5") (pinfunction "+IN_5") (pintype "input"))
      (node (ref "R51") (pin "2") (pinfunction "2_2") (pintype "passive"))
    )
    (net (code "41") (name "Net-(IC6B--IN)") (class "Default")
      (node (ref "IC6") (pin "6") (pinfunction "-IN_6") (pintype "input"))
      (node (ref "R56") (pin "2") (pinfunction "2_2") (pintype "passive"))
    )
    (net (code "42") (name "Net-(IC6B-OUT)") (class "Default")
      (node (ref "C37") (pin "2") (pinfunction "2_2") (pintype "passive"))
      (node (ref "IC6") (pin "7") (pinfunction "OUT_7") (pintype "output"))
      (node (ref "R55") (pin "1") (pinfunction "1_1") (pintype "passive"))
    )
    (net (code "43") (name "Net-(IC6C-+IN)") (class "Default")
      (node (ref "IC6") (pin "10") (pinfunction "+IN_10") (pintype "input"))
      (node (ref "R44") (pin "2-2") (pinfunction "S_2-2") (pintype "passive"))
      (node (ref "R46") (pin "1") (pinfunction "1_1") (pintype "passive"))
    )
    (net (code "44") (name "Net-(IC6C--IN)") (class "Default")
      (node (ref "IC6") (pin "9") (pinfunction "-IN_9") (pintype "input"))
      (node (ref "R54") (pin "2") (pinfunction "2_2") (pintype "passive"))
      (node (ref "R57") (pin "2") (pinfunction "2_2") (pintype "passive"))
      (node (ref "R60") (pin "1") (pinfunction "1_1") (pintype "passive"))
    )
    (net (code "45") (name "Net-(IC6C-OUT)") (class "Default")
      (node (ref "IC6") (pin "8") (pinfunction "OUT_8") (pintype "output"))
      (node (ref "IC8") (pin "2") (pinfunction "IN_2") (pintype "input"))
    )
    (net (code "46") (name "Net-(IC6D-+IN)") (class "Default")
      (node (ref "C38") (pin "1") (pinfunction "1_1") (pintype "passive"))
      (node (ref "IC6") (pin "12") (pinfunction "+IN_12") (pintype "input"))
      (node (ref "R52") (pin "2") (pinfunction "2_2") (pintype "passive"))
    )
    (net (code "47") (name "Net-(IC6D--IN)") (class "Default")
      (node (ref "IC6") (pin "13") (pinfunction "-IN_13") (pintype "input"))
      (node (ref "R58") (pin "2") (pinfunction "2_2") (pintype "passive"))
    )
    (net (code "48") (name "Net-(IC6D-OUT)") (class "Default")
      (node (ref "C38") (pin "2") (pinfunction "2_2") (pintype "passive"))
      (node (ref "IC6") (pin "14") (pinfunction "OUT_14") (pintype "output"))
      (node (ref "R57") (pin "1") (pinfunction "1_1") (pintype "passive"))
    )
    (net (code "49") (name "Net-(R9A-S)") (class "Default")
      (node (ref "R10") (pin "1") (pinfunction "1_1") (pintype "passive"))
      (node (ref "R13") (pin "2") (pinfunction "2_2") (pintype "passive"))
      (node (ref "R9") (pin "1-2") (pinfunction "S_1-2") (pintype "passive"))
    )
    (net (code "50") (name "Net-(R9B-S)") (class "Default")
      (node (ref "R11") (pin "1") (pinfunction "1_1") (pintype "passive"))
      (node (ref "R14") (pin "2") (pinfunction "2_2") (pintype "passive"))
      (node (ref "R9") (pin "2-2") (pinfunction "S_2-2") (pintype "passive"))
    )
    (net (code "51") (name "Net-(R22A-S)") (class "Default")
      (node (ref "R22") (pin "1-2") (pinfunction "S_1-2") (pintype "passive"))
      (node (ref "R27") (pin "1") (pinfunction "1_1") (pintype "passive"))
      (node (ref "R28") (pin "2") (pinfunction "2_2") (pintype "passive"))
    )
    (net (code "52") (name "Net-(R29-Pad1)") (class "Default")
      (node (ref "R29") (pin "1") (pinfunction "1_1") (pintype "passive"))
      (node (ref "U$17") (pin "P$1") (pinfunction "P$1_P$1") (pintype "bidirectional"))
    )
    (net (code "53") (name "Net-(R30-Pad1)") (class "Default")
      (node (ref "R30") (pin "1") (pinfunction "1_1") (pintype "passive"))
      (node (ref "U$19") (pin "P$1") (pinfunction "P$1_P$1") (pintype "bidirectional"))
    )
    (net (code "54") (name "Net-(R31-Pad1)") (class "Default")
      (node (ref "R31") (pin "1") (pinfunction "1_1") (pintype "passive"))
      (node (ref "U$14") (pin "P$1") (pinfunction "P$1_P$1") (pintype "bidirectional"))
    )
    (net (code "55") (name "Net-(R32-Pad1)") (class "Default")
      (node (ref "R32") (pin "1") (pinfunction "1_1") (pintype "passive"))
      (node (ref "U$16") (pin "P$1") (pinfunction "P$1_P$1") (pintype "bidirectional"))
    )
    (net (code "56") (name "Net-(U$1A-S)") (class "Default")
      (node (ref "C9") (pin "1") (pinfunction "1_1") (pintype "passive"))
      (node (ref "S3") (pin "P$2") (pinfunction "P$2_P$2") (pintype "passive"))
      (node (ref "U$1") (pin "SB") (pinfunction "S_SB") (pintype "bidirectional"))
    )
    (net (code "57") (name "Net-(U$1B-S)") (class "Default")
      (node (ref "C7") (pin "1") (pinfunction "1_1") (pintype "passive"))
      (node (ref "S1") (pin "P$2") (pinfunction "P$2_P$2") (pintype "passive"))
      (node (ref "U$1") (pin "ST") (pinfunction "S_ST") (pintype "bidirectional"))
    )
    (net (code "58") (name "Net-(U$2A-S)") (class "Default")
      (node (ref "C10") (pin "1") (pinfunction "1_1") (pintype "passive"))
      (node (ref "S4") (pin "P$2") (pinfunction "P$2_P$2") (pintype "passive"))
      (node (ref "U$2") (pin "SB") (pinfunction "S_SB") (pintype "bidirectional"))
    )
    (net (code "59") (name "Net-(U$2B-S)") (class "Default")
      (node (ref "C8") (pin "1") (pinfunction "1_1") (pintype "passive"))
      (node (ref "S2") (pin "P$2") (pinfunction "P$2_P$2") (pintype "passive"))
      (node (ref "U$2") (pin "ST") (pinfunction "S_ST") (pintype "bidirectional"))
    )
    (net (code "60") (name "Net-(U$3A-R)") (class "Default")
      (node (ref "R64") (pin "1") (pinfunction "1_1") (pintype "passive"))
      (node (ref "U$3") (pin "RB") (pinfunction "R_RB") (pintype "bidirectional"))
    )
    (net (code "61") (name "Net-(U$3A-S)") (class "Default")
      (node (ref "R63") (pin "1") (pinfunction "1_1") (pintype "passive"))
      (node (ref "U$3") (pin "SB") (pinfunction "S_SB") (pintype "bidirectional"))
    )
    (net (code "62") (name "Net-(U$3B-R)") (class "Default")
      (node (ref "R62") (pin "1") (pinfunction "1_1") (pintype "passive"))
      (node (ref "U$3") (pin "RT") (pinfunction "R_RT") (pintype "bidirectional"))
    )
    (net (code "63") (name "Net-(U$3B-S)") (class "Default")
      (node (ref "R61") (pin "1") (pinfunction "1_1") (pintype "passive"))
      (node (ref "U$3") (pin "ST") (pinfunction "S_ST") (pintype "bidirectional"))
    )
    (net (code "64") (name "Net-(U$4-FB)") (class "Default")
      (node (ref "C34") (pin "1") (pinfunction "1_1") (pintype "passive"))
      (node (ref "R49") (pin "1") (pinfunction "1_1") (pintype "passive"))
      (node (ref "R50") (pin "2") (pinfunction "2_2") (pintype "passive"))
      (node (ref "U$4") (pin "7") (pinfunction "FB_7") (pintype "bidirectional"))
    )
    (net (code "65") (name "Net-(U$4-NR{slash}SS)") (class "Default")
      (node (ref "C30") (pin "2") (pinfunction "2_2") (pintype "passive"))
      (node (ref "U$4") (pin "2") (pinfunction "NR/SS_2") (pintype "bidirectional"))
    )
    (net (code "66") (name "Net-(U$5-SENSE)") (class "Default")
      (node (ref "C33") (pin "1") (pinfunction "1_1") (pintype "passive"))
      (node (ref "R47") (pin "1") (pinfunction "1_1") (pintype "passive"))
      (node (ref "R48") (pin "2") (pinfunction "2_2") (pintype "passive"))
      (node (ref "U$5") (pin "5") (pinfunction "SENSE_5") (pintype "output"))
    )
    (net (code "67") (name "Net-(U$6B-T)") (class "Default")
      (node (ref "C11") (pin "1") (pinfunction "1_1") (pintype "passive"))
      (node (ref "S5") (pin "P$2") (pinfunction "P$2_P$2") (pintype "passive"))
      (node (ref "U$6") (pin "TT") (pinfunction "T_TT") (pintype "bidirectional"))
    )
    (net (code "68") (name "Net-(U1-IN)") (class "Default")
      (node (ref "R20") (pin "1") (pinfunction "1_1") (pintype "passive"))
      (node (ref "U1") (pin "P4") (pinfunction "IN_P4") (pintype "input"))
    )
    (net (code "69") (name "Net-(U1-OUT+)") (class "Default")
      (node (ref "R29") (pin "2") (pinfunction "2_2") (pintype "passive"))
      (node (ref "U1") (pin "P7") (pinfunction "SENSE+_P7") (pintype "input"))
      (node (ref "U1") (pin "P8") (pinfunction "OUT+_P8") (pintype "output"))
    )
    (net (code "70") (name "Net-(U1-OUT-)") (class "Default")
      (node (ref "R30") (pin "2") (pinfunction "2_2") (pintype "passive"))
      (node (ref "U1") (pin "P1") (pinfunction "OUT-_P1") (pintype "output"))
      (node (ref "U1") (pin "P2") (pinfunction "SENSE-_P2") (pintype "input"))
    )
    (net (code "71") (name "Net-(U2-IN)") (class "Default")
      (node (ref "R21") (pin "1") (pinfunction "1_1") (pintype "passive"))
      (node (ref "U2") (pin "P4") (pinfunction "IN_P4") (pintype "input"))
    )
    (net (code "72") (name "Net-(U2-OUT+)") (class "Default")
      (node (ref "R31") (pin "2") (pinfunction "2_2") (pintype "passive"))
      (node (ref "U2") (pin "P7") (pinfunction "SENSE+_P7") (pintype "input"))
      (node (ref "U2") (pin "P8") (pinfunction "OUT+_P8") (pintype "output"))
    )
    (net (code "73") (name "Net-(U2-OUT-)") (class "Default")
      (node (ref "R32") (pin "2") (pinfunction "2_2") (pintype "passive"))
      (node (ref "U2") (pin "P1") (pinfunction "OUT-_P1") (pintype "output"))
      (node (ref "U2") (pin "P2") (pinfunction "SENSE-_P2") (pintype "input"))
    )
    (net (code "74") (name "Net-(U3-IN)") (class "Default")
      (node (ref "R36") (pin "1") (pinfunction "1_1") (pintype "passive"))
      (node (ref "U3") (pin "P4") (pinfunction "IN_P4") (pintype "input"))
    )
    (net (code "75") (name "Net-(U3-OUT+)") (class "Default")
      (node (ref "R61") (pin "2") (pinfunction "2_2") (pintype "passive"))
      (node (ref "U3") (pin "P7") (pinfunction "SENSE+_P7") (pintype "input"))
      (node (ref "U3") (pin "P8") (pinfunction "OUT+_P8") (pintype "output"))
    )
    (net (code "76") (name "Net-(U3-OUT-)") (class "Default")
      (node (ref "R62") (pin "2") (pinfunction "2_2") (pintype "passive"))
      (node (ref "U3") (pin "P1") (pinfunction "OUT-_P1") (pintype "output"))
      (node (ref "U3") (pin "P2") (pinfunction "SENSE-_P2") (pintype "input"))
    )
    (net (code "77") (name "Net-(U4-IN)") (class "Default")
      (node (ref "R37") (pin "1") (pinfunction "1_1") (pintype "passive"))
      (node (ref "U4") (pin "P4") (pinfunction "IN_P4") (pintype "input"))
    )
    (net (code "78") (name "Net-(U4-OUT+)") (class "Default")
      (node (ref "R63") (pin "2") (pinfunction "2_2") (pintype "passive"))
      (node (ref "U4") (pin "P7") (pinfunction "SENSE+_P7") (pintype "input"))
      (node (ref "U4") (pin "P8") (pinfunction "OUT+_P8") (pintype "output"))
    )
    (net (code "79") (name "Net-(U4-OUT-)") (class "Default")
      (node (ref "R64") (pin "2") (pinfunction "2_2") (pintype "passive"))
      (node (ref "U4") (pin "P1") (pinfunction "OUT-_P1") (pintype "output"))
      (node (ref "U4") (pin "P2") (pinfunction "SENSE-_P2") (pintype "input"))
    )
    (net (code "80") (name "V+") (class "Default")
      (node (ref "C2") (pin "1") (pinfunction "1_1") (pintype "passive"))
      (node (ref "C20") (pin "1") (pinfunction "1_1") (pintype "passive"))
      (node (ref "C22") (pin "1") (pinfunction "1_1") (pintype "passive"))
      (node (ref "C24") (pin "1") (pinfunction "1_1") (pintype "passive"))
      (node (ref "C33") (pin "2") (pinfunction "2_2") (pintype "passive"))
      (node (ref "C35") (pin "+") (pinfunction "+_+") (pintype "passive"))
      (node (ref "C39") (pin "1") (pinfunction "1_1") (pintype "passive"))
      (node (ref "C4") (pin "1") (pinfunction "1_1") (pintype "passive"))
      (node (ref "C40") (pin "1") (pinfunction "1_1") (pintype "passive"))
      (node (ref "C41") (pin "1") (pinfunction "1_1") (pintype "passive"))
      (node (ref "C42") (pin "1") (pinfunction "1_1") (pintype "passive"))
      (node (ref "C47") (pin "1") (pinfunction "1_1") (pintype "passive"))
      (node (ref "C49") (pin "1") (pinfunction "1_1") (pintype "passive"))
      (node (ref "C5") (pin "1") (pinfunction "1_1") (pintype "passive"))
      (node (ref "IC1") (pin "11") (pinfunction "V+_11") (pintype "power_in"))
      (node (ref "IC2") (pin "8") (pinfunction "V+_8") (pintype "power_in"))
      (node (ref "IC3") (pin "4") (pinfunction "V+_4") (pintype "power_in"))
      (node (ref "IC4") (pin "8") (pinfunction "V+_8") (pintype "power_in"))
      (node (ref "IC5") (pin "8") (pinfunction "V+_8") (pintype "power_in"))
      (node (ref "IC6") (pin "4") (pinfunction "V+_4") (pintype "power_in"))
      (node (ref "IC7") (pin "5") (pinfunction "VCC_5") (pintype "power_in"))
      (node (ref "IC8") (pin "5") (pinfunction "VCC_5") (pintype "power_in"))
      (node (ref "R47") (pin "2") (pinfunction "2_2") (pintype "passive"))
      (node (ref "U$5") (pin "4") (pinfunction "OUT_4") (pintype "power_in"))
      (node (ref "U1") (pin "P6") (pinfunction "V+_P6") (pintype "power_in"))
      (node (ref "U2") (pin "P6") (pinfunction "V+_P6") (pintype "power_in"))
      (node (ref "U3") (pin "P6") (pinfunction "V+_P6") (pintype "power_in"))
      (node (ref "U4") (pin "P6") (pinfunction "V+_P6") (pintype "power_in"))
    )
    (net (code "81") (name "V-") (class "Default")
      (node (ref "C1") (pin "2") (pinfunction "2_2") (pintype "passive"))
      (node (ref "C21") (pin "2") (pinfunction "2_2") (pintype "passive"))
      (node (ref "C23") (pin "2") (pinfunction "2_2") (pintype "passive"))
      (node (ref "C25") (pin "2") (pinfunction "2_2") (pintype "passive"))
      (node (ref "C3") (pin "2") (pinfunction "2_2") (pintype "passive"))
      (node (ref "C34") (pin "2") (pinfunction "2_2") (pintype "passive"))
      (node (ref "C36") (pin "-") (pinfunction "-_-") (pintype "passive"))
      (node (ref "C43") (pin "1") (pinfunction "1_1") (pintype "passive"))
      (node (ref "C44") (pin "1") (pinfunction "1_1") (pintype "passive"))
      (node (ref "C45") (pin "1") (pinfunction "1_1") (pintype "passive"))
      (node (ref "C46") (pin "1") (pinfunction "1_1") (pintype "passive"))
      (node (ref "C48") (pin "2") (pinfunction "2_2") (pintype "passive"))
      (node (ref "C50") (pin "2") (pinfunction "2_2") (pintype "passive"))
      (node (ref "C6") (pin "1") (pinfunction "1_1") (pintype "passive"))
      (node (ref "IC1") (pin "4") (pinfunction "V-_4") (pintype "power_in"))
      (node (ref "IC2") (pin "4") (pinfunction "V-_4") (pintype "power_in"))
      (node (ref "IC3") (pin "11") (pinfunction "V-_11") (pintype "power_in"))
      (node (ref "IC4") (pin "4") (pinfunction "V-_4") (pintype "power_in"))
      (node (ref "IC5") (pin "4") (pinfunction "V-_4") (pintype "power_in"))
      (node (ref "IC6") (pin "11") (pinfunction "V-_11") (pintype "power_in"))
      (node (ref "IC7") (pin "1") (pinfunction "BW_1") (pintype "input"))
      (node (ref "IC7") (pin "3") (pinfunction "VEE_3") (pintype "power_in"))
      (node (ref "IC7") (pin "TH@1") (pinfunction "VEE_TH@1") (pintype "power_in"))
      (node (ref "IC7") (pin "TH@2") (pinfunction "VEE_TH@2") (pintype "power_in"))
      (node (ref "IC8") (pin "1") (pinfunction "BW_1") (pintype "input"))
      (node (ref "IC8") (pin "3") (pinfunction "VEE_3") (pintype "power_in"))
      (node (ref "IC8") (pin "TH@1") (pinfunction "VEE_TH@1") (pintype "power_in"))
      (node (ref "IC8") (pin "TH@2") (pinfunction "VEE_TH@2") (pintype "power_in"))
      (node (ref "R49") (pin "2") (pinfunction "2_2") (pintype "passive"))
      (node (ref "U$4") (pin "6") (pinfunction "OUT_6") (pintype "bidirectional"))
      (node (ref "U1") (pin "P5") (pinfunction "V-_P5") (pintype "power_in"))
      (node (ref "U2") (pin "P5") (pinfunction "V-_P5") (pintype "power_in"))
      (node (ref "U3") (pin "P5") (pinfunction "V-_P5") (pintype "power_in"))
      (node (ref "U4") (pin "P5") (pinfunction "V-_P5") (pintype "power_in"))
    )
    (net (code "82") (name "unconnected-(IC1-NC-Pad1)") (class "Default")
      (node (ref "IC1") (pin "1") (pinfunction "NC_1") (pintype "no_connect"))
    )
    (net (code "83") (name "unconnected-(IC1-NC-Pad7)") (class "Default")
      (node (ref "IC1") (pin "7") (pinfunction "NC_7") (pintype "no_connect"))
    )
    (net (code "84") (name "unconnected-(U$1A-R-PadRB)") (class "Default")
      (node (ref "U$1") (pin "RB") (pinfunction "R_RB") (pintype "bidirectional"))
    )
    (net (code "85") (name "unconnected-(U$1A-RN-PadRNB)") (class "Default")
      (node (ref "U$1") (pin "RNB") (pinfunction "RN_RNB") (pintype "bidirectional"))
    )
    (net (code "86") (name "unconnected-(U$1A-SN-PadSNB)") (class "Default")
      (node (ref "U$1") (pin "SNB") (pinfunction "SN_SNB") (pintype "bidirectional"))
    )
    (net (code "87") (name "unconnected-(U$1A-TN-PadTNB)") (class "Default")
      (node (ref "U$1") (pin "TNB") (pinfunction "TN_TNB") (pintype "bidirectional"))
    )
    (net (code "88") (name "unconnected-(U$1B-R-PadRT)") (class "Default")
      (node (ref "U$1") (pin "RT") (pinfunction "R_RT") (pintype "bidirectional"))
    )
    (net (code "89") (name "unconnected-(U$1B-RN-PadRNT)") (class "Default")
      (node (ref "U$1") (pin "RNT") (pinfunction "RN_RNT") (pintype "bidirectional"))
    )
    (net (code "90") (name "unconnected-(U$1B-SN-PadSNT)") (class "Default")
      (node (ref "U$1") (pin "SNT") (pinfunction "SN_SNT") (pintype "bidirectional"))
    )
    (net (code "91") (name "unconnected-(U$1B-TN-PadTNT)") (class "Default")
      (node (ref "U$1") (pin "TNT") (pinfunction "TN_TNT") (pintype "bidirectional"))
    )
    (net (code "92") (name "unconnected-(U$2A-R-PadRB)") (class "Default")
      (node (ref "U$2") (pin "RB") (pinfunction "R_RB") (pintype "bidirectional"))
    )
    (net (code "93") (name "unconnected-(U$2A-RN-PadRNB)") (class "Default")
      (node (ref "U$2") (pin "RNB") (pinfunction "RN_RNB") (pintype "bidirectional"))
    )
    (net (code "94") (name "unconnected-(U$2A-SN-PadSNB)") (class "Default")
      (node (ref "U$2") (pin "SNB") (pinfunction "SN_SNB") (pintype "bidirectional"))
    )
    (net (code "95") (name "unconnected-(U$2A-TN-PadTNB)") (class "Default")
      (node (ref "U$2") (pin "TNB") (pinfunction "TN_TNB") (pintype "bidirectional"))
    )
    (net (code "96") (name "unconnected-(U$2B-R-PadRT)") (class "Default")
      (node (ref "U$2") (pin "RT") (pinfunction "R_RT") (pintype "bidirectional"))
    )
    (net (code "97") (name "unconnected-(U$2B-RN-PadRNT)") (class "Default")
      (node (ref "U$2") (pin "RNT") (pinfunction "RN_RNT") (pintype "bidirectional"))
    )
    (net (code "98") (name "unconnected-(U$2B-SN-PadSNT)") (class "Default")
      (node (ref "U$2") (pin "SNT") (pinfunction "SN_SNT") (pintype "bidirectional"))
    )
    (net (code "99") (name "unconnected-(U$2B-TN-PadTNT)") (class "Default")
      (node (ref "U$2") (pin "TNT") (pinfunction "TN_TNT") (pintype "bidirectional"))
    )
    (net (code "100") (name "unconnected-(U$3A-RN-PadRNB)") (class "Default")
      (node (ref "U$3") (pin "RNB") (pinfunction "RN_RNB") (pintype "bidirectional"))
    )
    (net (code "101") (name "unconnected-(U$3A-SN-PadSNB)") (class "Default")
      (node (ref "U$3") (pin "SNB") (pinfunction "SN_SNB") (pintype "bidirectional"))
    )
    (net (code "102") (name "unconnected-(U$3A-TN-PadTNB)") (class "Default")
      (node (ref "U$3") (pin "TNB") (pinfunction "TN_TNB") (pintype "bidirectional"))
    )
    (net (code "103") (name "unconnected-(U$3B-RN-PadRNT)") (class "Default")
      (node (ref "U$3") (pin "RNT") (pinfunction "RN_RNT") (pintype "bidirectional"))
    )
    (net (code "104") (name "unconnected-(U$3B-SN-PadSNT)") (class "Default")
      (node (ref "U$3") (pin "SNT") (pinfunction "SN_SNT") (pintype "bidirectional"))
    )
    (net (code "105") (name "unconnected-(U$3B-TN-PadTNT)") (class "Default")
      (node (ref "U$3") (pin "TNT") (pinfunction "TN_TNT") (pintype "bidirectional"))
    )
    (net (code "106") (name "unconnected-(U$6A-RN-PadRNB)") (class "Default")
      (node (ref "U$6") (pin "RNB") (pinfunction "RN_RNB") (pintype "bidirectional"))
    )
    (net (code "107") (name "unconnected-(U$6A-SN-PadSNB)") (class "Default")
      (node (ref "U$6") (pin "SNB") (pinfunction "SN_SNB") (pintype "bidirectional"))
    )
    (net (code "108") (name "unconnected-(U$6A-TN-PadTNB)") (class "Default")
      (node (ref "U$6") (pin "TNB") (pinfunction "TN_TNB") (pintype "bidirectional"))
    )
    (net (code "109") (name "unconnected-(U$6B-R-PadRT)") (class "Default")
      (node (ref "U$6") (pin "RT") (pinfunction "R_RT") (pintype "bidirectional"))
    )
    (net (code "110") (name "unconnected-(U$6B-RN-PadRNT)") (class "Default")
      (node (ref "U$6") (pin "RNT") (pinfunction "RN_RNT") (pintype "bidirectional"))
    )
    (net (code "111") (name "unconnected-(U$6B-SN-PadSNT)") (class "Default")
      (node (ref "U$6") (pin "SNT") (pinfunction "SN_SNT") (pintype "bidirectional"))
    )
    (net (code "112") (name "unconnected-(U$6B-TN-PadTNT)") (class "Default")
      (node (ref "U$6") (pin "TNT") (pinfunction "TN_TNT") (pintype "bidirectional"))
    )
  )
)
